# schSPI.net
KiCad netlist of a schematic drawn in Altium Designer
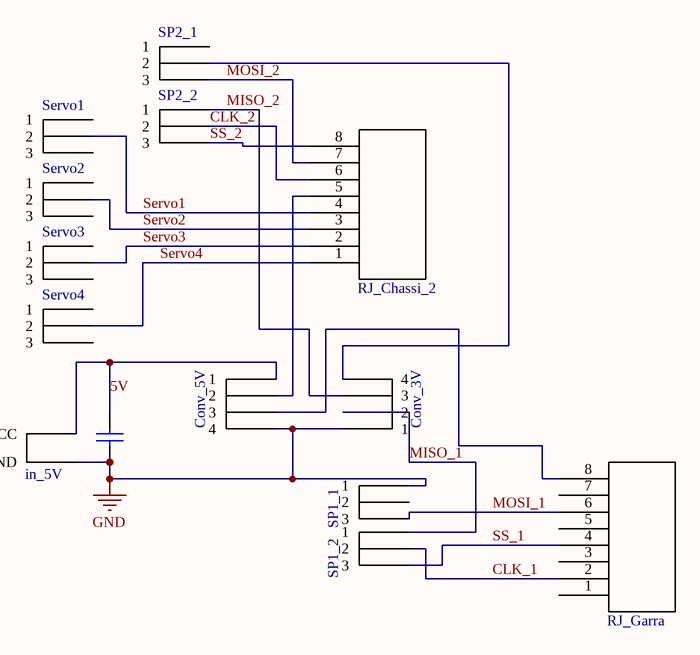
[diagram p0: schSPI.SchDoc]

(export (version "E")
  (design (tool "Eeschema 10.0.6"))
  (components
    (comp (ref "C2")
      (value "Cap")
      (footprint "RAD-0.3")
      (description "Capacitor")
      (fields (field (name "PUBLISHER") "Altium Limited"))
      (libsource (lib "Miscellaneous Devices") (part "Cap"))
    )
    (comp (ref "Conv_3V")
      (value "KK4")
      (footprint "4-vias")
      (libsource (lib "Componentes_Open") (part "KK4Vias"))
    )
    (comp (ref "Conv_5V")
      (value "KK4")
      (footprint "4-vias")
      (libsource (lib "Componentes_Open") (part "KK4Vias"))
    )
    (comp (ref "in_5V")
      (value "Jack")
      (footprint "JACK J4")
      (libsource (lib "Componentes_Open") (part "Jack"))
    )
    (comp (ref "RJ_Chassi_2")
      (value "RJ45")
      (footprint "RJ45_90")
      (libsource (lib "Componentes_Open") (part "RJ45_90"))
    )
    (comp (ref "RJ_Garra")
      (value "RJ45")
      (footprint "RJ45_Simples")
      (libsource (lib "Componentes_Open") (part "RJ45"))
    )
    (comp (ref "Servo1")
      (value "KK3")
      (footprint "3-vias")
      (libsource (lib "Componentes_Open") (part "KK3Vias"))
    )
    (comp (ref "Servo2")
      (value "KK3")
      (footprint "3-vias")
      (libsource (lib "Componentes_Open") (part "KK3Vias"))
    )
    (comp (ref "Servo3")
      (value "KK3")
      (footprint "3-vias")
      (libsource (lib "Componentes_Open") (part "KK3Vias"))
    )
    (comp (ref "Servo4")
      (value "KK3")
      (footprint "3-vias")
      (libsource (lib "Componentes_Open") (part "KK3Vias"))
    )
    (comp (ref "SP1_1")
      (value "KK3")
      (footprint "3-vias")
      (libsource (lib "Componentes_Open") (part "KK3Vias"))
    )
    (comp (ref "SP1_2")
      (value "KK3")
      (footprint "3-vias")
      (libsource (lib "Componentes_Open") (part "KK3Vias"))
    )
    (comp (ref "SP2_1")
      (value "KK3")
      (footprint "3-vias")
      (libsource (lib "Componentes_Open") (part "KK3Vias"))
    )
    (comp (ref "SP2_2")
      (value "KK3")
      (footprint "3-vias")
      (libsource (lib "Componentes_Open") (part "KK3Vias"))
    )
  )
  (nets
    (net (code "1") (name "/5V") (class "Default")
      (node (ref "C2") (pin "2") (pinfunction "2_2") (pintype "passive"))
      (node (ref "Conv_5V") (pin "1") (pinfunction "1_1") (pintype "passive"))
      (node (ref "in_5V") (pin "1") (pinfunction "VCC_1") (pintype "passive"))
    )
    (net (code "2") (name "/CLK_1") (class "Default")
      (node (ref "RJ_Garra") (pin "2") (pinfunction "2_2") (pintype "passive"))
      (node (ref "SP1_2") (pin "2") (pinfunction "2_2") (pintype "passive"))
    )
    (net (code "3") (name "/CLK_2") (class "Default")
      (node (ref "RJ_Chassi_2") (pin "6") (pinfunction "6_6") (pintype "passive"))
      (node (ref "SP2_2") (pin "2") (pinfunction "2_2") (pintype "passive"))
    )
    (net (code "4") (name "/MISO_1") (class "Default")
      (node (ref "Conv_3V") (pin "2") (pinfunction "2_2") (pintype "passive"))
      (node (ref "SP1_2") (pin "1") (pinfunction "1_1") (pintype "passive"))
    )
    (net (code "5") (name "/MISO_2") (class "Default")
      (node (ref "Conv_3V") (pin "3") (pinfunction "3_3") (pintype "passive"))
      (node (ref "SP2_2") (pin "1") (pinfunction "1_1") (pintype "passive"))
    )
    (net (code "6") (name "/MOSI_1") (class "Default")
      (node (ref "RJ_Garra") (pin "6") (pinfunction "6_6") (pintype "passive"))
      (node (ref "SP1_1") (pin "3") (pinfunction "3_3") (pintype "passive"))
    )
    (net (code "7") (name "/MOSI_2") (class "Default")
      (node (ref "RJ_Chassi_2") (pin "7") (pinfunction "7_7") (pintype "passive"))
      (node (ref "SP2_1") (pin "3") (pinfunction "3_3") (pintype "passive"))
    )
    (net (code "8") (name "/SS_1") (class "Default")
      (node (ref "RJ_Garra") (pin "4") (pinfunction "4_4") (pintype "passive"))
      (node (ref "SP1_2") (pin "3") (pinfunction "3_3") (pintype "passive"))
    )
    (net (code "9") (name "/SS_2") (class "Default")
      (node (ref "RJ_Chassi_2") (pin "8") (pinfunction "8_8") (pintype "passive"))
      (node (ref "SP2_2") (pin "3") (pinfunction "3_3") (pintype "passive"))
    )
    (net (code "10") (name "/Servo1") (class "Default")
      (node (ref "RJ_Chassi_2") (pin "4") (pinfunction "4_4") (pintype "passive"))
      (node (ref "Servo1") (pin "2") (pinfunction "2_2") (pintype "passive"))
    )
    (net (code "11") (name "/Servo2") (class "Default")
      (node (ref "RJ_Chassi_2") (pin "3") (pinfunction "3_3") (pintype "passive"))
      (node (ref "Servo2") (pin "2") (pinfunction "2_2") (pintype "passive"))
    )
    (net (code "12") (name "/Servo3") (class "Default")
      (node (ref "RJ_Chassi_2") (pin "2") (pinfunction "2_2") (pintype "passive"))
      (node (ref "Servo3") (pin "2") (pinfunction "2_2") (pintype "passive"))
    )
    (net (code "13") (name "/Servo4") (class "Default")
      (node (ref "RJ_Chassi_2") (pin "1") (pinfunction "9_1") (pintype "passive"))
      (node (ref "Servo4") (pin "2") (pinfunction "2_2") (pintype "passive"))
    )
    (net (code "14") (name "GND") (class "Default")
      (node (ref "C2") (pin "1") (pinfunction "1_1") (pintype "passive"))
      (node (ref "Conv_3V") (pin "1") (pinfunction "1_1") (pintype "passive"))
      (node (ref "Conv_5V") (pin "4") (pinfunction "4_4") (pintype "passive"))
      (node (ref "SP1_1") (pin "1") (pinfunction "1_1") (pintype "passive"))
      (node (ref "in_5V") (pin "2") (pinfunction "GND_2") (pintype "passive"))
    )
    (net (code "15") (name "Net-(Conv_3V-Pad4)") (class "Default")
      (node (ref "Conv_3V") (pin "4") (pinfunction "4_4") (pintype "passive"))
      (node (ref "SP2_1") (pin "2") (pinfunction "2_2") (pintype "passive"))
    )
    (net (code "16") (name "Net-(Conv_5V-Pad2)") (class "Default")
      (node (ref "Conv_5V") (pin "2") (pinfunction "2_2") (pintype "passive"))
      (node (ref "RJ_Chassi_2") (pin "5") (pinfunction "5_5") (pintype "passive"))
    )
    (net (code "17") (name "Net-(Conv_5V-Pad3)") (class "Default")
      (node (ref "Conv_5V") (pin "3") (pinfunction "3_3") (pintype "passive"))
      (node (ref "RJ_Garra") (pin "8") (pinfunction "8_8") (pintype "passive"))
    )
    (net (code "18") (name "unconnected-(RJ_Garra-9-Pad1)") (class "Default")
      (node (ref "RJ_Garra") (pin "1") (pinfunction "9_1") (pintype "passive"))
    )
    (net (code "19") (name "unconnected-(RJ_Garra-Pad3)") (class "Default")
      (node (ref "RJ_Garra") (pin "3") (pinfunction "3_3") (pintype "passive"))
    )
    (net (code "20") (name "unconnected-(RJ_Garra-Pad5)") (class "Default")
      (node (ref "RJ_Garra") (pin "5") (pinfunction "5_5") (pintype "passive"))
    )
    (net (code "21") (name "unconnected-(RJ_Garra-Pad7)") (class "Default")
      (node (ref "RJ_Garra") (pin "7") (pinfunction "7_7") (pintype "passive"))
    )
    (net (code "22") (name "unconnected-(SP1_1-Pad2)") (class "Default")
      (node (ref "SP1_1") (pin "2") (pinfunction "2_2") (pintype "passive"))
    )
    (net (code "23") (name "unconnected-(SP2_1-Pad1)") (class "Default")
      (node (ref "SP2_1") (pin "1") (pinfunction "1_1") (pintype "passive"))
    )
    (net (code "24") (name "unconnected-(Servo1-Pad1)") (class "Default")
      (node (ref "Servo1") (pin "1") (pinfunction "1_1") (pintype "passive"))
    )
    (net (code "25") (name "unconnected-(Servo1-Pad3)") (class "Default")
      (node (ref "Servo1") (pin "3") (pinfunction "3_3") (pintype "passive"))
    )
    (net (code "26") (name "unconnected-(Servo2-Pad1)") (class "Default")
      (node (ref "Servo2") (pin "1") (pinfunction "1_1") (pintype "passive"))
    )
    (net (code "27") (name "unconnected-(Servo2-Pad3)") (class "Default")
      (node (ref "Servo2") (pin "3") (pinfunction "3_3") (pintype "passive"))
    )
    (net (code "28") (name "unconnected-(Servo3-Pad1)") (class "Default")
      (node (ref "Servo3") (pin "1") (pinfunction "1_1") (pintype "passive"))
    )
    (net (code "29") (name "unconnected-(Servo3-Pad3)") (class "Default")
      (node (ref "Servo3") (pin "3") (pinfunction "3_3") (pintype "passive"))
    )
    (net (code "30") (name "unconnected-(Servo4-Pad1)") (class "Default")
      (node (ref "Servo4") (pin "1") (pinfunction "1_1") (pintype "passive"))
    )
    (net (code "31") (name "unconnected-(Servo4-Pad3)") (class "Default")
      (node (ref "Servo4") (pin "3") (pinfunction "3_3") (pintype "passive"))
    )
  )
)
